# Qwiic_GPS-RTK-SMA_-_ublox_ZED-F9P.net
KiCad netlist of a schematic drawn in EAGLE
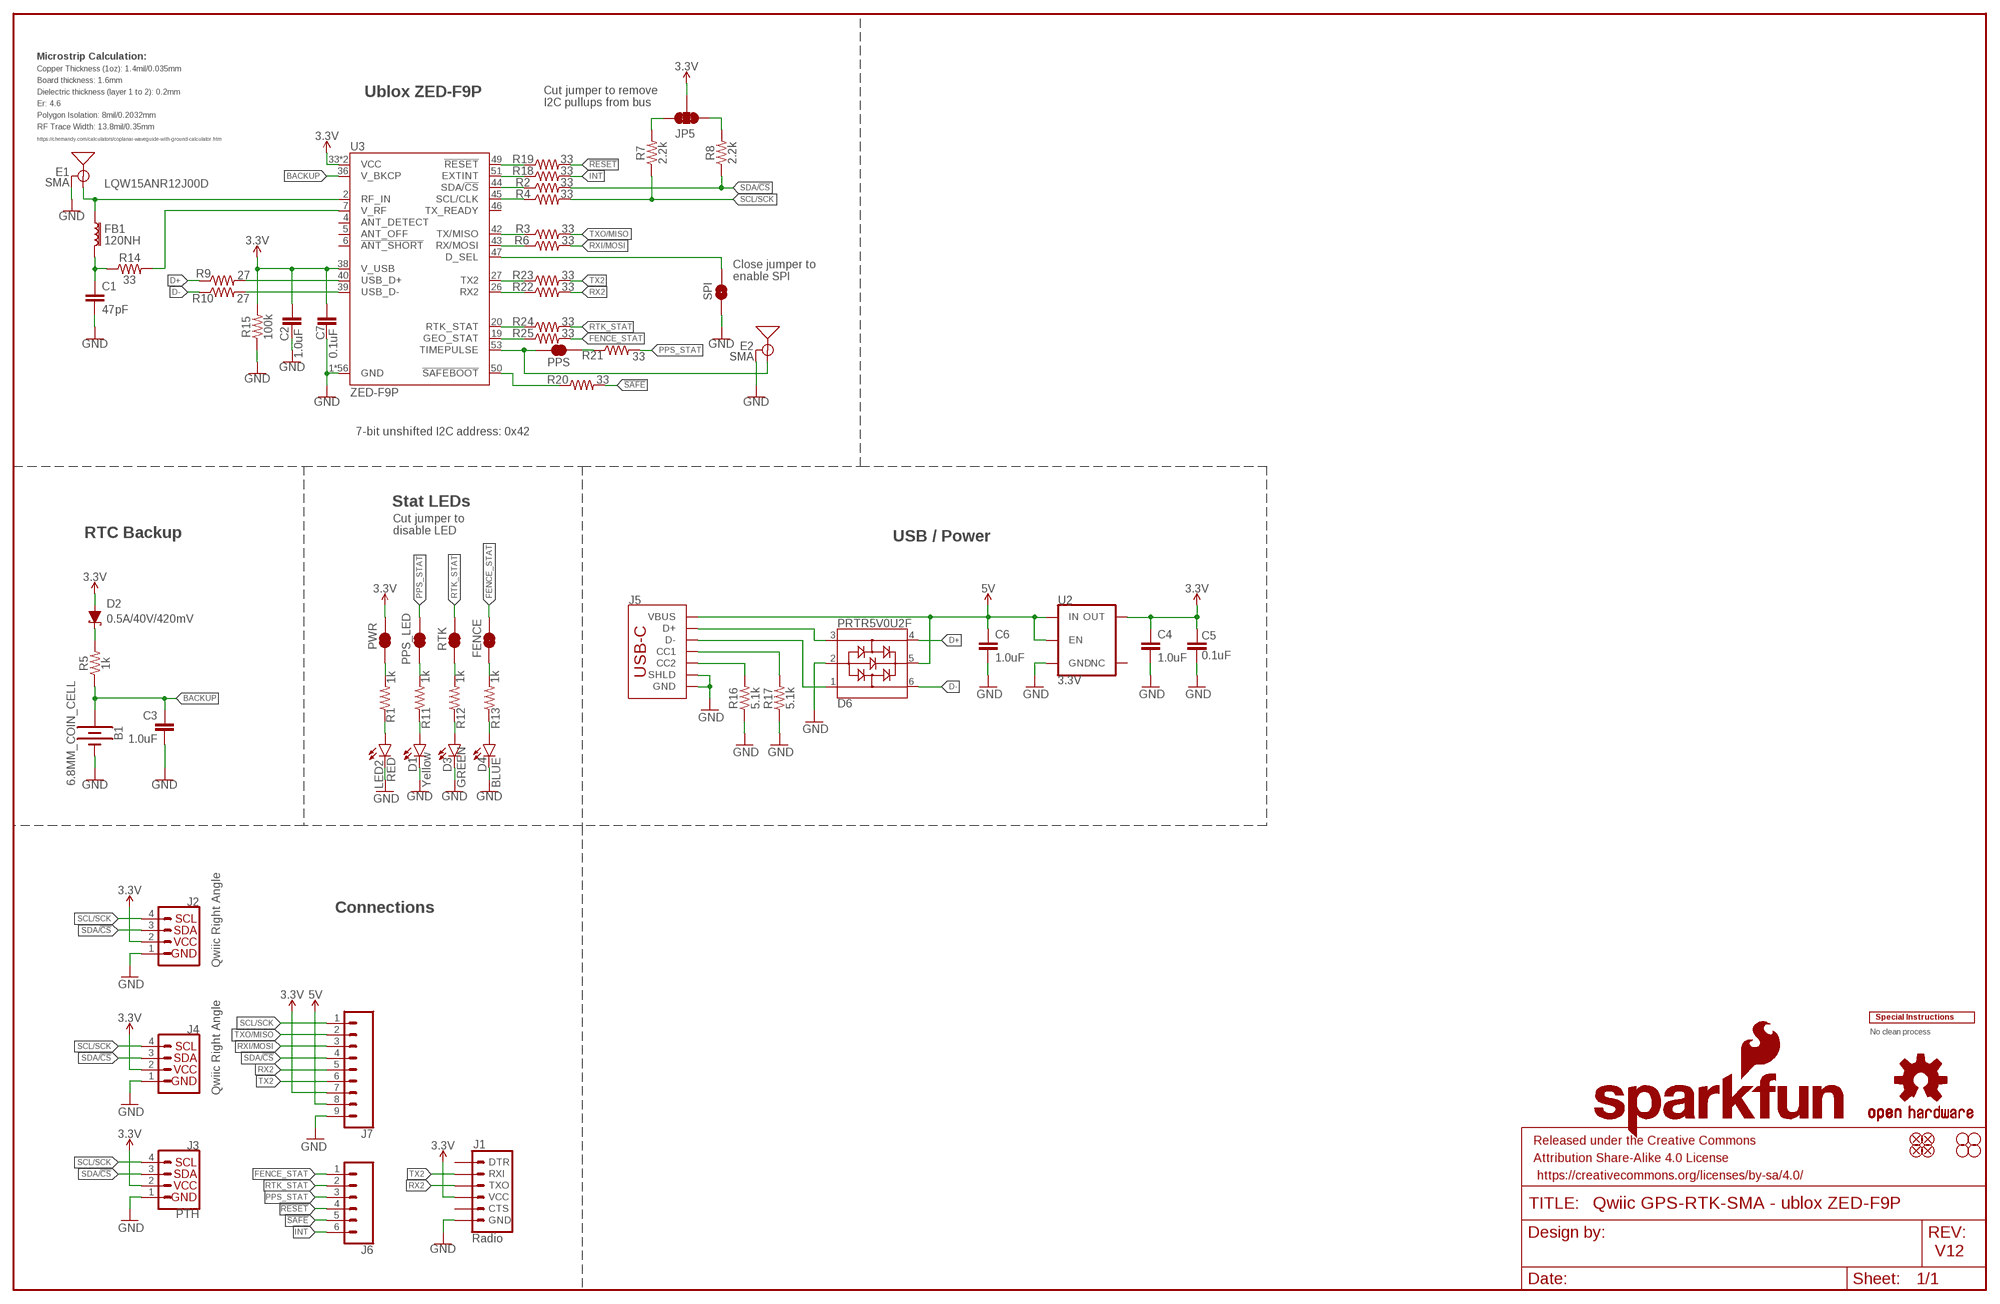
[diagram p0: schematic, sheet 1]

(export (version "E")
  (design (tool "Eeschema 10.0.6"))
  (components
    (comp (ref "B1")
      (value "6.8MM_COIN_CELL")
      (footprint "eagle-import:ML414H_IV01E")
      (libsource (lib "eagle-import") (part "ML414H_IV01E_BATTERY"))
    )
    (comp (ref "C1")
      (value "47pF")
      (footprint "eagle-import:0402")
      (libsource (lib "eagle-import") (part "47PF-0402-25V-5%-X7R"))
    )
    (comp (ref "C2")
      (value "1.0uF")
      (footprint "eagle-import:0603")
      (libsource (lib "eagle-import") (part "1.0UF-0603-16V-10%-X7R"))
    )
    (comp (ref "C3")
      (value "1.0uF")
      (footprint "eagle-import:0603")
      (libsource (lib "eagle-import") (part "1.0UF-0603-16V-10%-X7R"))
    )
    (comp (ref "C4")
      (value "1.0uF")
      (footprint "eagle-import:0603")
      (libsource (lib "eagle-import") (part "1.0UF-0603-16V-10%-X7R"))
    )
    (comp (ref "C5")
      (value "0.1uF")
      (footprint "eagle-import:0603")
      (libsource (lib "eagle-import") (part "0.1UF-0603-25V-5%"))
    )
    (comp (ref "C6")
      (value "1.0uF")
      (footprint "eagle-import:0603")
      (libsource (lib "eagle-import") (part "1.0UF-0603-16V-10%-X7R"))
    )
    (comp (ref "C7")
      (value "0.1uF")
      (footprint "eagle-import:0603")
      (libsource (lib "eagle-import") (part "0.1UF-0603-25V-5%"))
    )
    (comp (ref "D1")
      (value "Yellow")
      (footprint "eagle-import:LED-0603")
      (libsource (lib "eagle-import") (part "LED-YELLOW0603"))
    )
    (comp (ref "D2")
      (value "0.5A/40V/420mV")
      (footprint "eagle-import:SOD-323")
      (libsource (lib "eagle-import") (part "DIODE-SCHOTTKY-PMEG4005EJ"))
    )
    (comp (ref "D3")
      (value "GREEN")
      (footprint "eagle-import:LED-0603")
      (libsource (lib "eagle-import") (part "LED-GREEN0603"))
    )
    (comp (ref "D4")
      (value "BLUE")
      (footprint "eagle-import:LED-0603")
      (libsource (lib "eagle-import") (part "LED-BLUE0603"))
    )
    (comp (ref "D6")
      (value "PRTR5V0U2F")
      (footprint "eagle-import:SOT886")
      (libsource (lib "eagle-import") (part "PRTR5V0U2F"))
    )
    (comp (ref "E1")
      (value "SMA")
      (footprint "eagle-import:SMA-EDGE")
      (libsource (lib "eagle-import") (part "ANTENNA-GROUNDEDEDGE_SMA"))
    )
    (comp (ref "E2")
      (value "SMA")
      (footprint "eagle-import:SMA-EDGE")
      (libsource (lib "eagle-import") (part "ANTENNA-GROUNDEDEDGE_SMA"))
    )
    (comp (ref "FB1")
      (value "120NH")
      (footprint "eagle-import:0402_MURATA")
      (libsource (lib "eagle-import") (part "FERRITE_BEAD_GNSS"))
    )
    (comp (ref "FENCE")
      (value "JUMPER-SMT_2_NC_TRACE_SILK")
      (footprint "eagle-import:SMT-JUMPER_2_NC_TRACE_SILK")
      (libsource (lib "eagle-import") (part "JUMPER-SMT_2_NC_TRACE_SILK"))
    )
    (comp (ref "FRAME2")
      (value "FRAME-LEDGER")
      (footprint "eagle-import:CREATIVE_COMMONS")
      (libsource (lib "eagle-import") (part "FRAME-LEDGER"))
    )
    (comp (ref "J1")
      (value "Radio")
      (footprint "eagle-import:1X06_NO_SILK")
      (libsource (lib "eagle-import") (part "6_PIN_SERIAL_TARGET_NO_SILK"))
    )
    (comp (ref "J2")
      (value "Qwiic Right Angle")
      (footprint "eagle-import:JST04_1MM_RA")
      (libsource (lib "eagle-import") (part "I2C_STANDARDQWIIC"))
    )
    (comp (ref "J3")
      (value "PTH")
      (footprint "eagle-import:1X04_NO_SILK")
      (libsource (lib "eagle-import") (part "SparkX_I2C_STANDARD_NO_SILK"))
    )
    (comp (ref "J4")
      (value "Qwiic Right Angle")
      (footprint "eagle-import:JST04_1MM_RA")
      (libsource (lib "eagle-import") (part "I2C_STANDARDQWIIC"))
    )
    (comp (ref "J5")
      (value "USB_C_2-LAYER_PADS")
      (footprint "eagle-import:USB-C-16P-2LAYER-PADS")
      (libsource (lib "eagle-import") (part "USB_C_2-LAYER_PADS"))
    )
    (comp (ref "J6")
      (value "CONN_06NO_SILK_FEMALE_PTH")
      (footprint "eagle-import:1X06_NO_SILK")
      (libsource (lib "eagle-import") (part "CONN_06NO_SILK_FEMALE_PTH"))
    )
    (comp (ref "J7")
      (value "CONN_09NO_SILK")
      (footprint "eagle-import:1X09_NO_SILK")
      (libsource (lib "eagle-import") (part "CONN_09NO_SILK"))
    )
    (comp (ref "JP5")
      (value "JUMPER-SMT_3_2-NC_TRACE_SILK")
      (footprint "eagle-import:SMT-JUMPER_3_2-NC_TRACE_SILK")
      (libsource (lib "eagle-import") (part "JUMPER-SMT_3_2-NC_TRACE_SILK"))
    )
    (comp (ref "JP21")
      (value "FIDUCIALUFIDUCIAL")
      (footprint "eagle-import:MICRO-FIDUCIAL")
      (libsource (lib "eagle-import") (part "FIDUCIALUFIDUCIAL"))
    )
    (comp (ref "JP31")
      (value "STAND-OFF")
      (footprint "eagle-import:STAND-OFF")
      (libsource (lib "eagle-import") (part "STAND-OFF"))
    )
    (comp (ref "JP41")
      (value "STAND-OFF")
      (footprint "eagle-import:STAND-OFF")
      (libsource (lib "eagle-import") (part "STAND-OFF"))
    )
    (comp (ref "JP61")
      (value "FIDUCIALUFIDUCIAL")
      (footprint "eagle-import:MICRO-FIDUCIAL")
      (libsource (lib "eagle-import") (part "FIDUCIALUFIDUCIAL"))
    )
    (comp (ref "JP71")
      (value "FIDUCIALUFIDUCIAL")
      (footprint "eagle-import:MICRO-FIDUCIAL")
      (libsource (lib "eagle-import") (part "FIDUCIALUFIDUCIAL"))
    )
    (comp (ref "JP81")
      (value "FIDUCIALUFIDUCIAL")
      (footprint "eagle-import:MICRO-FIDUCIAL")
      (libsource (lib "eagle-import") (part "FIDUCIALUFIDUCIAL"))
    )
    (comp (ref "JP91")
      (value "STAND-OFF")
      (footprint "eagle-import:STAND-OFF")
      (libsource (lib "eagle-import") (part "STAND-OFF"))
    )
    (comp (ref "JP101")
      (value "STAND-OFF")
      (footprint "eagle-import:STAND-OFF")
      (libsource (lib "eagle-import") (part "STAND-OFF"))
    )
    (comp (ref "LED2")
      (value "RED")
      (footprint "eagle-import:LED-0603")
      (libsource (lib "eagle-import") (part "LED-RED0603"))
    )
    (comp (ref "LOGO1")
      (value "OSHW-LOGOMINI")
      (footprint "eagle-import:OSHW-LOGO-MINI")
      (libsource (lib "eagle-import") (part "OSHW-LOGOMINI"))
    )
    (comp (ref "LOGO2")
      (value "SFE_LOGO_NAME_FLAME.1_INCH")
      (footprint "eagle-import:SFE_LOGO_NAME_FLAME_.1")
      (libsource (lib "eagle-import") (part "SFE_LOGO_NAME_FLAME.1_INCH"))
    )
    (comp (ref "PPS")
      (value "JUMPER-SMT_2_NC_TRACE_SILK")
      (footprint "eagle-import:SMT-JUMPER_2_NC_TRACE_SILK")
      (libsource (lib "eagle-import") (part "JUMPER-SMT_2_NC_TRACE_SILK"))
    )
    (comp (ref "PPS_LED")
      (value "JUMPER-SMT_2_NC_TRACE_SILK")
      (footprint "eagle-import:SMT-JUMPER_2_NC_TRACE_SILK")
      (libsource (lib "eagle-import") (part "JUMPER-SMT_2_NC_TRACE_SILK"))
    )
    (comp (ref "PWR")
      (value "JUMPER-SMT_2_NC_TRACE_SILK")
      (footprint "eagle-import:SMT-JUMPER_2_NC_TRACE_SILK")
      (libsource (lib "eagle-import") (part "JUMPER-SMT_2_NC_TRACE_SILK"))
    )
    (comp (ref "R1")
      (value "1k")
      (footprint "eagle-import:0603")
      (libsource (lib "eagle-import") (part "1KOHM-0603-1/10W-1%"))
    )
    (comp (ref "R2")
      (value "33")
      (footprint "eagle-import:0603")
      (libsource (lib "eagle-import") (part "33OHM-0603-1/10W-1%"))
    )
    (comp (ref "R3")
      (value "33")
      (footprint "eagle-import:0603")
      (libsource (lib "eagle-import") (part "33OHM-0603-1/10W-1%"))
    )
    (comp (ref "R4")
      (value "33")
      (footprint "eagle-import:0603")
      (libsource (lib "eagle-import") (part "33OHM-0603-1/10W-1%"))
    )
    (comp (ref "R5")
      (value "1k")
      (footprint "eagle-import:0603")
      (libsource (lib "eagle-import") (part "1KOHM-0603-1/10W-1%"))
    )
    (comp (ref "R6")
      (value "33")
      (footprint "eagle-import:0603")
      (libsource (lib "eagle-import") (part "33OHM-0603-1/10W-1%"))
    )
    (comp (ref "R7")
      (value "2.2k")
      (footprint "eagle-import:0603")
      (libsource (lib "eagle-import") (part "2.2KOHM-0603-1/10W-1%"))
    )
    (comp (ref "R8")
      (value "2.2k")
      (footprint "eagle-import:0603")
      (libsource (lib "eagle-import") (part "2.2KOHM-0603-1/10W-1%"))
    )
    (comp (ref "R9")
      (value "27")
      (footprint "eagle-import:0603")
      (libsource (lib "eagle-import") (part "27OHM-0603-1/10W-1%"))
    )
    (comp (ref "R10")
      (value "27")
      (footprint "eagle-import:0603")
      (libsource (lib "eagle-import") (part "27OHM-0603-1/10W-1%"))
    )
    (comp (ref "R11")
      (value "1k")
      (footprint "eagle-import:0603")
      (libsource (lib "eagle-import") (part "1KOHM-0603-1/10W-1%"))
    )
    (comp (ref "R12")
      (value "1k")
      (footprint "eagle-import:0603")
      (libsource (lib "eagle-import") (part "1KOHM-0603-1/10W-1%"))
    )
    (comp (ref "R13")
      (value "1k")
      (footprint "eagle-import:0603")
      (libsource (lib "eagle-import") (part "1KOHM-0603-1/10W-1%"))
    )
    (comp (ref "R14")
      (value "33")
      (footprint "eagle-import:0603")
      (libsource (lib "eagle-import") (part "33OHM-0603-1/10W-1%"))
    )
    (comp (ref "R15")
      (value "100k")
      (footprint "eagle-import:0603")
      (libsource (lib "eagle-import") (part "100KOHM-0603-1/10W-1%"))
    )
    (comp (ref "R16")
      (value "5.1k")
      (footprint "eagle-import:0603")
      (libsource (lib "eagle-import") (part "5.1KOHM5.1KOHM-0603-1/10W-1%"))
    )
    (comp (ref "R17")
      (value "5.1k")
      (footprint "eagle-import:0603")
      (libsource (lib "eagle-import") (part "5.1KOHM5.1KOHM-0603-1/10W-1%"))
    )
    (comp (ref "R18")
      (value "33")
      (footprint "eagle-import:0603")
      (libsource (lib "eagle-import") (part "33OHM-0603-1/10W-1%"))
    )
    (comp (ref "R19")
      (value "33")
      (footprint "eagle-import:0603")
      (libsource (lib "eagle-import") (part "33OHM-0603-1/10W-1%"))
    )
    (comp (ref "R20")
      (value "33")
      (footprint "eagle-import:0603")
      (libsource (lib "eagle-import") (part "33OHM-0603-1/10W-1%"))
    )
    (comp (ref "R21")
      (value "33")
      (footprint "eagle-import:0603")
      (libsource (lib "eagle-import") (part "33OHM-0603-1/10W-1%"))
    )
    (comp (ref "R22")
      (value "33")
      (footprint "eagle-import:0603")
      (libsource (lib "eagle-import") (part "33OHM-0603-1/10W-1%"))
    )
    (comp (ref "R23")
      (value "33")
      (footprint "eagle-import:0603")
      (libsource (lib "eagle-import") (part "33OHM-0603-1/10W-1%"))
    )
    (comp (ref "R24")
      (value "33")
      (footprint "eagle-import:0603")
      (libsource (lib "eagle-import") (part "33OHM-0603-1/10W-1%"))
    )
    (comp (ref "R25")
      (value "33")
      (footprint "eagle-import:0603")
      (libsource (lib "eagle-import") (part "33OHM-0603-1/10W-1%"))
    )
    (comp (ref "RTK")
      (value "JUMPER-SMT_2_NC_TRACE_SILK")
      (footprint "eagle-import:SMT-JUMPER_2_NC_TRACE_SILK")
      (libsource (lib "eagle-import") (part "JUMPER-SMT_2_NC_TRACE_SILK"))
    )
    (comp (ref "SPI")
      (value "JUMPER-SMT_2_NO_SILK")
      (footprint "eagle-import:SMT-JUMPER_2_NO_SILK")
      (libsource (lib "eagle-import") (part "JUMPER-SMT_2_NO_SILK"))
    )
    (comp (ref "U$2")
      (value "SPECIAL_INSTRUCTIONS-ORDERING")
      (footprint "eagle-import:ORDERING_INSTRUCTIONS")
      (libsource (lib "eagle-import") (part "SPECIAL_INSTRUCTIONS-ORDERING"))
    )
    (comp (ref "U2")
      (value "3.3V")
      (footprint "eagle-import:SOT23-5")
      (libsource (lib "eagle-import") (part "V_REG_AP2112K-3.3V"))
    )
    (comp (ref "U3")
      (value "ZED-F9P")
      (footprint "eagle-import:ZED-F9P")
      (libsource (lib "eagle-import") (part "ZED-F9P"))
    )
  )
  (nets
    (net (code "1") (name "/SDA{slash}~{CS}") (class "Default")
      (node (ref "J2") (pin "3") (pinfunction "3_3") (pintype "passive"))
      (node (ref "J3") (pin "3") (pinfunction "SDA_3") (pintype "passive"))
      (node (ref "J4") (pin "3") (pinfunction "3_3") (pintype "passive"))
      (node (ref "J7") (pin "4") (pinfunction "4_4") (pintype "passive"))
      (node (ref "R2") (pin "2") (pinfunction "2_2") (pintype "passive"))
      (node (ref "R8") (pin "1") (pinfunction "1_1") (pintype "passive"))
    )
    (net (code "2") (name "/~{RESET}") (class "Default")
      (node (ref "J6") (pin "4") (pinfunction "4_4") (pintype "passive"))
      (node (ref "R19") (pin "2") (pinfunction "2_2") (pintype "passive"))
    )
    (net (code "3") (name "/~{SAFE}") (class "Default")
      (node (ref "J6") (pin "5") (pinfunction "5_5") (pintype "passive"))
      (node (ref "R20") (pin "2") (pinfunction "2_2") (pintype "passive"))
    )
    (net (code "4") (name "3.3V") (class "Default")
      (node (ref "C2") (pin "1") (pinfunction "1_1") (pintype "passive"))
      (node (ref "C4") (pin "1") (pinfunction "1_1") (pintype "passive"))
      (node (ref "C5") (pin "2") (pinfunction "2_2") (pintype "passive"))
      (node (ref "C7") (pin "2") (pinfunction "2_2") (pintype "passive"))
      (node (ref "D2") (pin "A") (pinfunction "A_A") (pintype "passive"))
      (node (ref "J1") (pin "4") (pinfunction "VCC_4") (pintype "passive"))
      (node (ref "J2") (pin "2") (pinfunction "2_2") (pintype "power_in"))
      (node (ref "J3") (pin "2") (pinfunction "VCC_2") (pintype "power_in"))
      (node (ref "J4") (pin "2") (pinfunction "2_2") (pintype "power_in"))
      (node (ref "J7") (pin "7") (pinfunction "7_7") (pintype "passive"))
      (node (ref "JP5") (pin "2") (pinfunction "2_2") (pintype "passive"))
      (node (ref "PWR") (pin "2") (pinfunction "2_2") (pintype "passive"))
      (node (ref "R15") (pin "2") (pinfunction "2_2") (pintype "passive"))
      (node (ref "U2") (pin "5") (pinfunction "OUT_5") (pintype "passive"))
      (node (ref "U3") (pin "33") (pinfunction "VCC_33") (pintype "bidirectional"))
      (node (ref "U3") (pin "34") (pinfunction "VCC_34") (pintype "bidirectional"))
      (node (ref "U3") (pin "38") (pinfunction "V_USB_38") (pintype "bidirectional"))
    )
    (net (code "5") (name "5V") (class "Default")
      (node (ref "C6") (pin "1") (pinfunction "1_1") (pintype "passive"))
      (node (ref "D6") (pin "5") (pinfunction "5_5") (pintype "bidirectional"))
      (node (ref "J5") (pin "VBUS1") (pinfunction "VBUS_VBUS1") (pintype "bidirectional"))
      (node (ref "J5") (pin "VBUS2") (pinfunction "VBUS_VBUS2") (pintype "bidirectional"))
      (node (ref "J7") (pin "8") (pinfunction "8_8") (pintype "passive"))
      (node (ref "U2") (pin "1") (pinfunction "IN_1") (pintype "input"))
      (node (ref "U2") (pin "3") (pinfunction "EN_3") (pintype "input"))
    )
    (net (code "6") (name "BACKUP") (class "Default")
      (node (ref "B1") (pin "+") (pinfunction "+_+") (pintype "power_in"))
      (node (ref "C3") (pin "1") (pinfunction "1_1") (pintype "passive"))
      (node (ref "R5") (pin "1") (pinfunction "1_1") (pintype "passive"))
      (node (ref "U3") (pin "36") (pinfunction "V_BKCP_36") (pintype "bidirectional"))
    )
    (net (code "7") (name "D+") (class "Default")
      (node (ref "D6") (pin "4") (pinfunction "4_4") (pintype "bidirectional"))
      (node (ref "R9") (pin "1") (pinfunction "1_1") (pintype "passive"))
    )
    (net (code "8") (name "D-") (class "Default")
      (node (ref "D6") (pin "6") (pinfunction "6_6") (pintype "bidirectional"))
      (node (ref "R10") (pin "1") (pinfunction "1_1") (pintype "passive"))
    )
    (net (code "9") (name "FENCE_STAT") (class "Default")
      (node (ref "FENCE") (pin "2") (pinfunction "2_2") (pintype "passive"))
      (node (ref "J6") (pin "1") (pinfunction "1_1") (pintype "passive"))
      (node (ref "R25") (pin "2") (pinfunction "2_2") (pintype "passive"))
    )
    (net (code "10") (name "GND") (class "Default")
      (node (ref "B1") (pin "-") (pinfunction "-_-") (pintype "power_in"))
      (node (ref "C1") (pin "2") (pinfunction "2_2") (pintype "passive"))
      (node (ref "C2") (pin "2") (pinfunction "2_2") (pintype "passive"))
      (node (ref "C3") (pin "2") (pinfunction "2_2") (pintype "passive"))
      (node (ref "C4") (pin "2") (pinfunction "2_2") (pintype "passive"))
      (node (ref "C5") (pin "1") (pinfunction "1_1") (pintype "passive"))
      (node (ref "C6") (pin "2") (pinfunction "2_2") (pintype "passive"))
      (node (ref "C7") (pin "1") (pinfunction "1_1") (pintype "passive"))
      (node (ref "D1") (pin "C") (pinfunction "C_C") (pintype "passive"))
      (node (ref "D3") (pin "C") (pinfunction "C_C") (pintype "passive"))
      (node (ref "D4") (pin "C") (pinfunction "C_C") (pintype "passive"))
      (node (ref "D6") (pin "2") (pinfunction "2_2") (pintype "bidirectional"))
      (node (ref "E1") (pin "GND@0") (pinfunction "GND_GND@0") (pintype "bidirectional"))
      (node (ref "E1") (pin "GND@1") (pinfunction "GND_GND@1") (pintype "bidirectional"))
      (node (ref "E1") (pin "GND@2") (pinfunction "GND_GND@2") (pintype "bidirectional"))
      (node (ref "E1") (pin "GND@3") (pinfunction "GND_GND@3") (pintype "bidirectional"))
      (node (ref "E2") (pin "GND@0") (pinfunction "GND_GND@0") (pintype "bidirectional"))
      (node (ref "E2") (pin "GND@1") (pinfunction "GND_GND@1") (pintype "bidirectional"))
      (node (ref "E2") (pin "GND@2") (pinfunction "GND_GND@2") (pintype "bidirectional"))
      (node (ref "E2") (pin "GND@3") (pinfunction "GND_GND@3") (pintype "bidirectional"))
      (node (ref "J1") (pin "6") (pinfunction "GND_6") (pintype "passive"))
      (node (ref "J2") (pin "1") (pinfunction "1_1") (pintype "power_in"))
      (node (ref "J3") (pin "1") (pinfunction "GND_1") (pintype "power_in"))
      (node (ref "J4") (pin "1") (pinfunction "1_1") (pintype "power_in"))
      (node (ref "J5") (pin "GND") (pinfunction "GND_GND") (pintype "bidirectional"))
      (node (ref "J5") (pin "GND2") (pinfunction "GND_GND2") (pintype "bidirectional"))
      (node (ref "J5") (pin "SHLD1") (pinfunction "SHLD_SHLD1") (pintype "bidirectional"))
      (node (ref "J5") (pin "SHLD2") (pinfunction "SHLD_SHLD2") (pintype "bidirectional"))
      (node (ref "J5") (pin "SHLD3") (pinfunction "SHLD_SHLD3") (pintype "bidirectional"))
      (node (ref "J5") (pin "SHLD4") (pinfunction "SHLD_SHLD4") (pintype "bidirectional"))
      (node (ref "J7") (pin "9") (pinfunction "9_9") (pintype "passive"))
      (node (ref "LED2") (pin "C") (pinfunction "C_C") (pintype "passive"))
      (node (ref "R15") (pin "1") (pinfunction "1_1") (pintype "passive"))
      (node (ref "R16") (pin "1") (pinfunction "1_1") (pintype "passive"))
      (node (ref "R17") (pin "1") (pinfunction "1_1") (pintype "passive"))
      (node (ref "SPI") (pin "1") (pinfunction "1_1") (pintype "passive"))
      (node (ref "U2") (pin "2") (pinfunction "GND_2") (pintype "input"))
      (node (ref "U3") (pin "1") (pinfunction "GND_1") (pintype "bidirectional"))
      (node (ref "U3") (pin "100") (pinfunction "GND_100") (pintype "bidirectional"))
      (node (ref "U3") (pin "101") (pinfunction "GND_101") (pintype "bidirectional"))
      (node (ref "U3") (pin "102") (pinfunction "GND_102") (pintype "bidirectional"))
      (node (ref "U3") (pin "12") (pinfunction "GND_12") (pintype "bidirectional"))
      (node (ref "U3") (pin "14") (pinfunction "GND_14") (pintype "bidirectional"))
      (node (ref "U3") (pin "3") (pinfunction "GND_3") (pintype "bidirectional"))
      (node (ref "U3") (pin "32") (pinfunction "GND_32") (pintype "bidirectional"))
      (node (ref "U3") (pin "37") (pinfunction "GND_37") (pintype "bidirectional"))
      (node (ref "U3") (pin "41") (pinfunction "GND_41") (pintype "bidirectional"))
      (node (ref "U3") (pin "48") (pinfunction "GND_48") (pintype "bidirectional"))
      (node (ref "U3") (pin "55") (pinfunction "GND_55") (pintype "bidirectional"))
      (node (ref "U3") (pin "56") (pinfunction "GND_56") (pintype "bidirectional"))
      (node (ref "U3") (pin "57") (pinfunction "GND_57") (pintype "bidirectional"))
      (node (ref "U3") (pin "58") (pinfunction "GND_58") (pintype "bidirectional"))
      (node (ref "U3") (pin "59") (pinfunction "GND_59") (pintype "bidirectional"))
      (node (ref "U3") (pin "60") (pinfunction "GND_60") (pintype "bidirectional"))
      (node (ref "U3") (pin "61") (pinfunction "GND_61") (pintype "bidirectional"))
      (node (ref "U3") (pin "62") (pinfunction "GND_62") (pintype "bidirectional"))
      (node (ref "U3") (pin "63") (pinfunction "GND_63") (pintype "bidirectional"))
      (node (ref "U3") (pin "64") (pinfunction "GND_64") (pintype "bidirectional"))
      (node (ref "U3") (pin "65") (pinfunction "GND_65") (pintype "bidirectional"))
      (node (ref "U3") (pin "66") (pinfunction "GND_66") (pintype "bidirectional"))
      (node (ref "U3") (pin "67") (pinfunction "GND_67") (pintype "bidirectional"))
      (node (ref "U3") (pin "68") (pinfunction "GND_68") (pintype "bidirectional"))
      (node (ref "U3") (pin "69") (pinfunction "GND_69") (pintype "bidirectional"))
      (node (ref "U3") (pin "70") (pinfunction "GND_70") (pintype "bidirectional"))
      (node (ref "U3") (pin "71") (pinfunction "GND_71") (pintype "bidirectional"))
      (node (ref "U3") (pin "72") (pinfunction "GND_72") (pintype "bidirectional"))
      (node (ref "U3") (pin "73") (pinfunction "GND_73") (pintype "bidirectional"))
      (node (ref "U3") (pin "74") (pinfunction "GND_74") (pintype "bidirectional"))
      (node (ref "U3") (pin "75") (pinfunction "GND_75") (pintype "bidirectional"))
      (node (ref "U3") (pin "76") (pinfunction "GND_76") (pintype "bidirectional"))
      (node (ref "U3") (pin "77") (pinfunction "GND_77") (pintype "bidirectional"))
      (node (ref "U3") (pin "78") (pinfunction "GND_78") (pintype "bidirectional"))
      (node (ref "U3") (pin "79") (pinfunction "GND_79") (pintype "bidirectional"))
      (node (ref "U3") (pin "80") (pinfunction "GND_80") (pintype "bidirectional"))
      (node (ref "U3") (pin "81") (pinfunction "GND_81") (pintype "bidirectional"))
      (node (ref "U3") (pin "82") (pinfunction "GND_82") (pintype "bidirectional"))
      (node (ref "U3") (pin "83") (pinfunction "GND_83") (pintype "bidirectional"))
      (node (ref "U3") (pin "84") (pinfunction "GND_84") (pintype "bidirectional"))
      (node (ref "U3") (pin "85") (pinfunction "GND_85") (pintype "bidirectional"))
      (node (ref "U3") (pin "86") (pinfunction "GND_86") (pintype "bidirectional"))
      (node (ref "U3") (pin "87") (pinfunction "GND_87") (pintype "bidirectional"))
      (node (ref "U3") (pin "88") (pinfunction "GND_88") (pintype "bidirectional"))
      (node (ref "U3") (pin "89") (pinfunction "GND_89") (pintype "bidirectional"))
      (node (ref "U3") (pin "90") (pinfunction "GND_90") (pintype "bidirectional"))
      (node (ref "U3") (pin "91") (pinfunction "GND_91") (pintype "bidirectional"))
      (node (ref "U3") (pin "92") (pinfunction "GND_92") (pintype "bidirectional"))
      (node (ref "U3") (pin "93") (pinfunction "GND_93") (pintype "bidirectional"))
      (node (ref "U3") (pin "94") (pinfunction "GND_94") (pintype "bidirectional"))
      (node (ref "U3") (pin "95") (pinfunction "GND_95") (pintype "bidirectional"))
      (node (ref "U3") (pin "96") (pinfunction "GND_96") (pintype "bidirectional"))
      (node (ref "U3") (pin "97") (pinfunction "GND_97") (pintype "bidirectional"))
      (node (ref "U3") (pin "98") (pinfunction "GND_98") (pintype "bidirectional"))
      (node (ref "U3") (pin "99") (pinfunction "GND_99") (pintype "bidirectional"))
    )
    (net (code "11") (name "INT") (class "Default")
      (node (ref "J6") (pin "6") (pinfunction "6_6") (pintype "passive"))
      (node (ref "R18") (pin "2") (pinfunction "2_2") (pintype "passive"))
    )
    (net (code "12") (name "Net-(D1-PadA)") (class "Default")
      (node (ref "D1") (pin "A") (pinfunction "A_A") (pintype "passive"))
      (node (ref "R11") (pin "1") (pinfunction "1_1") (pintype "passive"))
    )
    (net (code "13") (name "Net-(D2-PadC)") (class "Default")
      (node (ref "D2") (pin "C") (pinfunction "C_C") (pintype "passive"))
      (node (ref "R5") (pin "2") (pinfunction "2_2") (pintype "passive"))
    )
    (net (code "14") (name "Net-(D3-PadA)") (class "Default")
      (node (ref "D3") (pin "A") (pinfunction "A_A") (pintype "passive"))
      (node (ref "R12") (pin "1") (pinfunction "1_1") (pintype "passive"))
    )
    (net (code "15") (name "Net-(D4-PadA)") (class "Default")
      (node (ref "D4") (pin "A") (pinfunction "A_A") (pintype "passive"))
      (node (ref "R13") (pin "1") (pinfunction "1_1") (pintype "passive"))
    )
    (net (code "16") (name "Net-(D6-Pad1)") (class "Default")
      (node (ref "D6") (pin "1") (pinfunction "1_1") (pintype "bidirectional"))
      (node (ref "J5") (pin "A7") (pinfunction "D-_A7") (pintype "bidirectional"))
      (node (ref "J5") (pin "B7") (pinfunction "D-_B7") (pintype "bidirectional"))
    )
    (net (code "17") (name "Net-(D6-Pad3)") (class "Default")
      (node (ref "D6") (pin "3") (pinfunction "3_3") (pintype "bidirectional"))
      (node (ref "J5") (pin "A6") (pinfunction "D+_A6") (pintype "bidirectional"))
      (node (ref "J5") (pin "B6") (pinfunction "D+_B6") (pintype "bidirectional"))
    )
    (net (code "18") (name "Net-(E1-SIGNAL)") (class "Default")
      (node (ref "E1") (pin "SIG") (pinfunction "SIGNAL_SIG") (pintype "bidirectional"))
      (node (ref "FB1") (pin "P1") (pinfunction "1_P1") (pintype "passive"))
      (node (ref "U3") (pin "2") (pinfunction "RF_IN_2") (pintype "bidirectional"))
    )
    (net (code "19") (name "Net-(E2-SIGNAL)") (class "Default")
      (node (ref "E2") (pin "SIG") (pinfunction "SIGNAL_SIG") (pintype "bidirectional"))
      (node (ref "PPS") (pin "2") (pinfunction "2_2") (pintype "passive"))
      (node (ref "U3") (pin "53") (pinfunction "TIMEPULSE_53") (pintype "bidirectional"))
    )
    (net (code "20") (name "Net-(FB1-2)") (class "Default")
      (node (ref "C1") (pin "1") (pinfunction "1_1") (pintype "passive"))
      (node (ref "FB1") (pin "P2") (pinfunction "2_P2") (pintype "passive"))
      (node (ref "R14") (pin "1") (pinfunction "1_1") (pintype "passive"))
    )
    (net (code "21") (name "Net-(FENCE-Pad1)") (class "Default")
      (node (ref "FENCE") (pin "1") (pinfunction "1_1") (pintype "passive"))
      (node (ref "R13") (pin "2") (pinfunction "2_2") (pintype "passive"))
    )
    (net (code "22") (name "Net-(J5-CC1)") (class "Default")
      (node (ref "J5") (pin "A5") (pinfunction "CC1_A5") (pintype "bidirectional"))
      (node (ref "R17") (pin "2") (pinfunction "2_2") (pintype "passive"))
    )
    (net (code "23") (name "Net-(J5-CC2)") (class "Default")
      (node (ref "J5") (pin "B5") (pinfunction "CC2_B5") (pintype "bidirectional"))
      (node (ref "R16") (pin "2") (pinfunction "2_2") (pintype "passive"))
    )
    (net (code "24") (name "Net-(JP5-Pad1)") (class "Default")
      (node (ref "JP5") (pin "1") (pinfunction "1_1") (pintype "passive"))
      (node (ref "R8") (pin "2") (pinfunction "2_2") (pintype "passive"))
    )
    (net (code "25") (name "Net-(JP5-Pad3)") (class "Default")
      (node (ref "JP5") (pin "3") (pinfunction "3_3") (pintype "passive"))
      (node (ref "R7") (pin "2") (pinfunction "2_2") (pintype "passive"))
    )
    (net (code "26") (name "Net-(LED2-PadA)") (class "Default")
      (node (ref "LED2") (pin "A") (pinfunction "A_A") (pintype "passive"))
      (node (ref "R1") (pin "1") (pinfunction "1_1") (pintype "passive"))
    )
    (net (code "27") (name "Net-(PPS-Pad1)") (class "Default")
      (node (ref "PPS") (pin "1") (pinfunction "1_1") (pintype "passive"))
      (node (ref "R21") (pin "1") (pinfunction "1_1") (pintype "passive"))
    )
    (net (code "28") (name "Net-(PPS_LED-Pad1)") (class "Default")
      (node (ref "PPS_LED") (pin "1") (pinfunction "1_1") (pintype "passive"))
      (node (ref "R11") (pin "2") (pinfunction "2_2") (pintype "passive"))
    )
    (net (code "29") (name "Net-(PWR-Pad1)") (class "Default")
      (node (ref "PWR") (pin "1") (pinfunction "1_1") (pintype "passive"))
      (node (ref "R1") (pin "2") (pinfunction "2_2") (pintype "passive"))
    )
    (net (code "30") (name "Net-(R12-Pad2)") (class "Default")
      (node (ref "R12") (pin "2") (pinfunction "2_2") (pintype "passive"))
      (node (ref "RTK") (pin "1") (pinfunction "1_1") (pintype "passive"))
    )
    (net (code "31") (name "Net-(U3-D_SEL)") (class "Default")
      (node (ref "SPI") (pin "2") (pinfunction "2_2") (pintype "passive"))
      (node (ref "U3") (pin "47") (pinfunction "D_SEL_47") (pintype "bidirectional"))
    )
    (net (code "32") (name "Net-(U3-EXTINT)") (class "Default")
      (node (ref "R18") (pin "1") (pinfunction "1_1") (pintype "passive"))
      (node (ref "U3") (pin "51") (pinfunction "EXTINT_51") (pintype "bidirectional"))
    )
    (net (code "33") (name "Net-(U3-GEO_STAT)") (class "Default")
      (node (ref "R25") (pin "1") (pinfunction "1_1") (pintype "passive"))
      (node (ref "U3") (pin "19") (pinfunction "GEO_STAT_19") (pintype "bidirectional"))
    )
    (net (code "34") (name "Net-(U3-RTK_STAT)") (class "Default")
      (node (ref "R24") (pin "1") (pinfunction "1_1") (pintype "passive"))
      (node (ref "U3") (pin "20") (pinfunction "RTK_STAT_20") (pintype "bidirectional"))
    )
    (net (code "35") (name "Net-(U3-RX2)") (class "Default")
      (node (ref "R22") (pin "1") (pinfunction "1_1") (pintype "passive"))
      (node (ref "U3") (pin "26") (pinfunction "RX2_26") (pintype "bidirectional"))
    )
    (net (code "36") (name "Net-(U3-RX{slash}MOSI)") (class "Default")
      (node (ref "R6") (pin "1") (pinfunction "1_1") (pintype "passive"))
      (node (ref "U3") (pin "43") (pinfunction "RX/MOSI_43") (pintype "bidirectional"))
    )
    (net (code "37") (name "Net-(U3-SCL{slash}CLK)") (class "Default")
      (node (ref "R4") (pin "1") (pinfunction "1_1") (pintype "passive"))
      (node (ref "U3") (pin "45") (pinfunction "SCL/CLK_45") (pintype "bidirectional"))
    )
    (net (code "38") (name "Net-(U3-SDA{slash}~{CS})") (class "Default")
      (node (ref "R2") (pin "1") (pinfunction "1_1") (pintype "passive"))
      (node (ref "U3") (pin "44") (pinfunction "SDA/~{CS}_44") (pintype "bidirectional"))
    )
    (net (code "39") (name "Net-(U3-TX2)") (class "Default")
      (node (ref "R23") (pin "1") (pinfunction "1_1") (pintype "passive"))
      (node (ref "U3") (pin "27") (pinfunction "TX2_27") (pintype "bidirectional"))
    )
    (net (code "40") (name "Net-(U3-TX{slash}MISO)") (class "Default")
      (node (ref "R3") (pin "1") (pinfunction "1_1") (pintype "passive"))
      (node (ref "U3") (pin "42") (pinfunction "TX/MISO_42") (pintype "bidirectional"))
    )
    (net (code "41") (name "Net-(U3-USB_D+)") (class "Default")
      (node (ref "R9") (pin "2") (pinfunction "2_2") (pintype "passive"))
      (node (ref "U3") (pin "40") (pinfunction "USB_D+_40") (pintype "bidirectional"))
    )
    (net (code "42") (name "Net-(U3-USB_D-)") (class "Default")
      (node (ref "R10") (pin "2") (pinfunction "2_2") (pintype "passive"))
      (node (ref "U3") (pin "39") (pinfunction "USB_D-_39") (pintype "bidirectional"))
    )
    (net (code "43") (name "Net-(U3-V_RF)") (class "Default")
      (node (ref "R14") (pin "2") (pinfunction "2_2") (pintype "passive"))
      (node (ref "U3") (pin "7") (pinfunction "V_RF_7") (pintype "bidirectional"))
    )
    (net (code "44") (name "Net-(U3-~{RESET})") (class "Default")
      (node (ref "R19") (pin "1") (pinfunction "1_1") (pintype "passive"))
      (node (ref "U3") (pin "49") (pinfunction "~{RESET}_49") (pintype "bidirectional"))
    )
    (net (code "45") (name "Net-(U3-~{SAFEBOOT})") (class "Default")
      (node (ref "R20") (pin "1") (pinfunction "1_1") (pintype "passive"))
      (node (ref "U3") (pin "50") (pinfunction "~{SAFEBOOT}_50") (pintype "bidirectional"))
    )
    (net (code "46") (name "PPS_STAT") (class "Default")
      (node (ref "J6") (pin "3") (pinfunction "3_3") (pintype "passive"))
      (node (ref "PPS_LED") (pin "2") (pinfunction "2_2") (pintype "passive"))
      (node (ref "R21") (pin "2") (pinfunction "2_2") (pintype "passive"))
    )
    (net (code "47") (name "RTK_STAT") (class "Default")
      (node (ref "J6") (pin "2") (pinfunction "2_2") (pintype "passive"))
      (node (ref "R24") (pin "2") (pinfunction "2_2") (pintype "passive"))
      (node (ref "RTK") (pin "2") (pinfunction "2_2") (pintype "passive"))
    )
    (net (code "48") (name "RX2") (class "Default")
      (node (ref "J1") (pin "3") (pinfunction "TXO_3") (pintype "passive"))
      (node (ref "J7") (pin "5") (pinfunction "5_5") (pintype "passive"))
      (node (ref "R22") (pin "2") (pinfunction "2_2") (pintype "passive"))
    )
    (net (code "49") (name "RXI{slash}MOSI") (class "Default")
      (node (ref "J7") (pin "3") (pinfunction "3_3") (pintype "passive"))
      (node (ref "R6") (pin "2") (pinfunction "2_2") (pintype "passive"))
    )
    (net (code "50") (name "SCL{slash}SCK") (class "Default")
      (node (ref "J2") (pin "4") (pinfunction "4_4") (pintype "passive"))
      (node (ref "J3") (pin "4") (pinfunction "SCL_4") (pintype "passive"))
      (node (ref "J4") (pin "4") (pinfunction "4_4") (pintype "passive"))
      (node (ref "J7") (pin "1") (pinfunction "1_1") (pintype "passive"))
      (node (ref "R4") (pin "2") (pinfunction "2_2") (pintype "passive"))
      (node (ref "R7") (pin "1") (pinfunction "1_1") (pintype "passive"))
    )
    (net (code "51") (name "TX2") (class "Default")
      (node (ref "J1") (pin "2") (pinfunction "RXI_2") (pintype "passive"))
      (node (ref "J7") (pin "6") (pinfunction "6_6") (pintype "passive"))
      (node (ref "R23") (pin "2") (pinfunction "2_2") (pintype "passive"))
    )
    (net (code "52") (name "TXO{slash}MISO") (class "Default")
      (node (ref "J7") (pin "2") (pinfunction "2_2") (pintype "passive"))
      (node (ref "R3") (pin "2") (pinfunction "2_2") (pintype "passive"))
    )
    (net (code "53") (name "unconnected-(J1-CTS-Pad5)") (class "Default")
      (node (ref "J1") (pin "5") (pinfunction "CTS_5") (pintype "passive"))
    )
    (net (code "54") (name "unconnected-(J1-DTR-Pad1)") (class "Default")
      (node (ref "J1") (pin "1") (pinfunction "DTR_1") (pintype "passive"))
    )
    (net (code "55") (name "unconnected-(U2-NC-Pad4)") (class "Default")
      (node (ref "U2") (pin "4") (pinfunction "NC_4") (pintype "no_connect"))
    )
    (net (code "56") (name "unconnected-(U3-ANT_DETECT-Pad4)") (class "Default")
      (node (ref "U3") (pin "4") (pinfunction "ANT_DETECT_4") (pintype "bidirectional"))
    )
    (net (code "57") (name "unconnected-(U3-ANT_OFF-Pad5)") (class "Default")
      (node (ref "U3") (pin "5") (pinfunction "ANT_OFF_5") (pintype "bidirectional"))
    )
    (net (code "58") (name "unconnected-(U3-TX_READY-Pad46)") (class "Default")
      (node (ref "U3") (pin "46") (pinfunction "TX_READY_46") (pintype "bidirectional"))
    )
    (net (code "59") (name "unconnected-(U3-~{ANT_SHORT}-Pad6)") (class "Default")
      (node (ref "U3") (pin "6") (pinfunction "~{ANT_SHORT}_6") (pintype "bidirectional"))
    )
  )
)
